# LP2951.net
KiCad netlist of a schematic drawn in Altium Designer
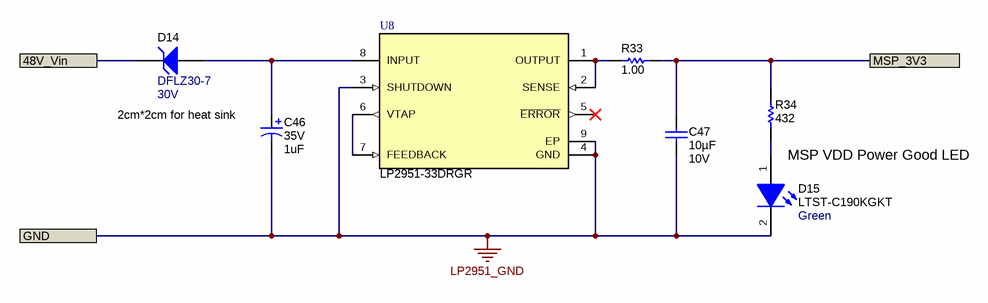
[diagram p0: LP2951.SchDoc]

(export (version "E")
  (design (tool "Eeschema 10.0.6"))
  (components
    (comp (ref "C46")
      (value "293D105X9035B2TE3")
      (footprint "3528-21")
      (description "CAP, TA, 1 uF, 35 V, +/- 10%, 5 ohm, SMD")
      (fields
        (field (name "MANUFACTURER") "Vishay-Sprague")
        (field (name "VDC_V") "35V")
        (field (name "VALUEDISPLAYED") "1uF")
        (field (name "PUBLISHER") "Texas Instruments")
      )
      (libsource (lib "Altium Vault - TI") (part "Cap_Polarized"))
    )
    (comp (ref "C47")
      (value "GRM188Z71A106MA73D")
      (footprint "0603")
      (description "CAP, CERM, 10 uF, 10 V, +/- 20%, X7R, 0603")
      (fields
        (field (name "MANUFACTURER") "MuRata")
        (field (name "CAP_F") "10µF")
        (field (name "VDC_V") "10V")
        (field (name "PUBLISHER") "Texas Instruments")
      )
      (libsource (lib "Altium Vault - TI") (part "Capacitor"))
    )
    (comp (ref "D14")
      (value "DFLZ30-7")
      (footprint "PowerDI123")
      (description "Diode, Zener, 30 V, 1 W, PowerDI123")
      (fields (field (name "ALTIUM_VALUE") "30V") (field (name "MANUFACTURER") "Diodes Inc."))
      (libsource (lib "Altium Vault - TI") (part "Zener"))
    )
    (comp (ref "D15")
      (value "LTST-C190KGKT")
      (footprint "LED_LTST-C190_G")
      (description "LED, Green, SMD")
      (fields (field (name "ALTIUM_VALUE") "Green") (field (name "MANUFACTURER") "Lite-On"))
      (libsource (lib "Altium Vault - TI") (part "LED"))
    )
    (comp (ref "R33")
      (value "CRCW06031R00FKEA")
      (footprint "0603")
      (description "RES, 1.00, 1%, 0.1 W, 0603")
      (fields
        (field (name "MANUFACTURER") "Vishay-Dale")
        (field (name "VALUEDISPLAYED") "1.00")
        (field (name "PUBLISHER") "Texas Instruments")
      )
      (libsource (lib "Altium Vault - TI") (part "Resistor"))
    )
    (comp (ref "R34")
      (value "CRCW0603432RFKEA")
      (footprint "0603")
      (description "RES, 432, 1%, 0.1 W, AEC-Q200 Grade 0, 0603")
      (fields (field (name "MANUFACTURER") "Vishay-Dale") (field (name "VALUEDISPLAYED") "432"))
      (libsource (lib "Altium Vault - TI") (part "Resistor"))
    )
    (comp (ref "U8")
      (value "LP2951-33DRGR")
      (footprint "DRG0008A")
      (fields (field (name "MANUFACTURER") "Texas Instruments") (field (name "PARTNUMBER") "LP2951-33DRGR"))
      (libsource (lib "Altium Vault - TI") (part "TI-LP2951-DRG8"))
    )
  )
  (nets
    (net (code "1") (name "/48V_Vin") (class "Default")
      (node (ref "D14") (pin "1") (pinfunction "K_1") (pintype "passive"))
    )
    (net (code "2") (name "/MSP_3V3") (class "Default")
      (node (ref "C47") (pin "1") (pinfunction "1_1") (pintype "passive"))
      (node (ref "R33") (pin "1") (pinfunction "1_1") (pintype "passive"))
      (node (ref "R34") (pin "2") (pinfunction "2_2") (pintype "passive"))
    )
    (net (code "3") (name "LP2951_GND") (class "Default")
      (node (ref "C46") (pin "2") (pinfunction "-_2") (pintype "passive"))
      (node (ref "C47") (pin "2") (pinfunction "2_2") (pintype "passive"))
      (node (ref "D15") (pin "2") (pinfunction "K_2") (pintype "passive"))
      (node (ref "U8") (pin "3") (pinfunction "SHUTDOWN_3") (pintype "input"))
      (node (ref "U8") (pin "4") (pinfunction "GND_4") (pintype "power_in"))
      (node (ref "U8") (pin "9") (pinfunction "EP_9") (pintype "passive"))
    )
    (net (code "4") (name "Net-(C46-+)") (class "Default")
      (node (ref "C46") (pin "1") (pinfunction "+_1") (pintype "passive"))
      (node (ref "D14") (pin "2") (pinfunction "A_2") (pintype "passive"))
      (node (ref "U8") (pin "8") (pinfunction "INPUT_8") (pintype "power_in"))
    )
    (net (code "5") (name "Net-(D15-A)") (class "Default")
      (node (ref "D15") (pin "1") (pinfunction "A_1") (pintype "passive"))
      (node (ref "R34") (pin "1") (pinfunction "1_1") (pintype "passive"))
    )
    (net (code "6") (name "Net-(U8-FEEDBACK)") (class "Default")
      (node (ref "U8") (pin "6") (pinfunction "VTAP_6") (pintype "output"))
      (node (ref "U8") (pin "7") (pinfunction "FEEDBACK_7") (pintype "input"))
    )
    (net (code "7") (name "Net-(U8-OUTPUT)") (class "Default")
      (node (ref "R33") (pin "2") (pinfunction "2_2") (pintype "passive"))
      (node (ref "U8") (pin "1") (pinfunction "OUTPUT_1") (pintype "power_in"))
      (node (ref "U8") (pin "2") (pinfunction "SENSE_2") (pintype "input"))
    )
    (net (code "8") (name "unconnected-(U8-~{ERROR}-Pad5)") (class "Default")
      (node (ref "U8") (pin "5") (pinfunction "~{ERROR}_5") (pintype "output+no_connect"))
    )
  )
)
